# Main_Board.net
KiCad netlist of a schematic drawn in EAGLE
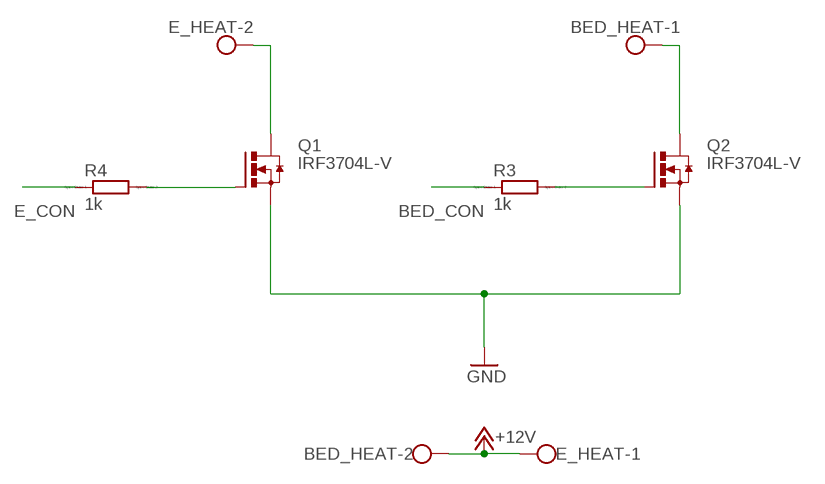
[diagram p0: schematic, sheet 1, part 1 of 2]
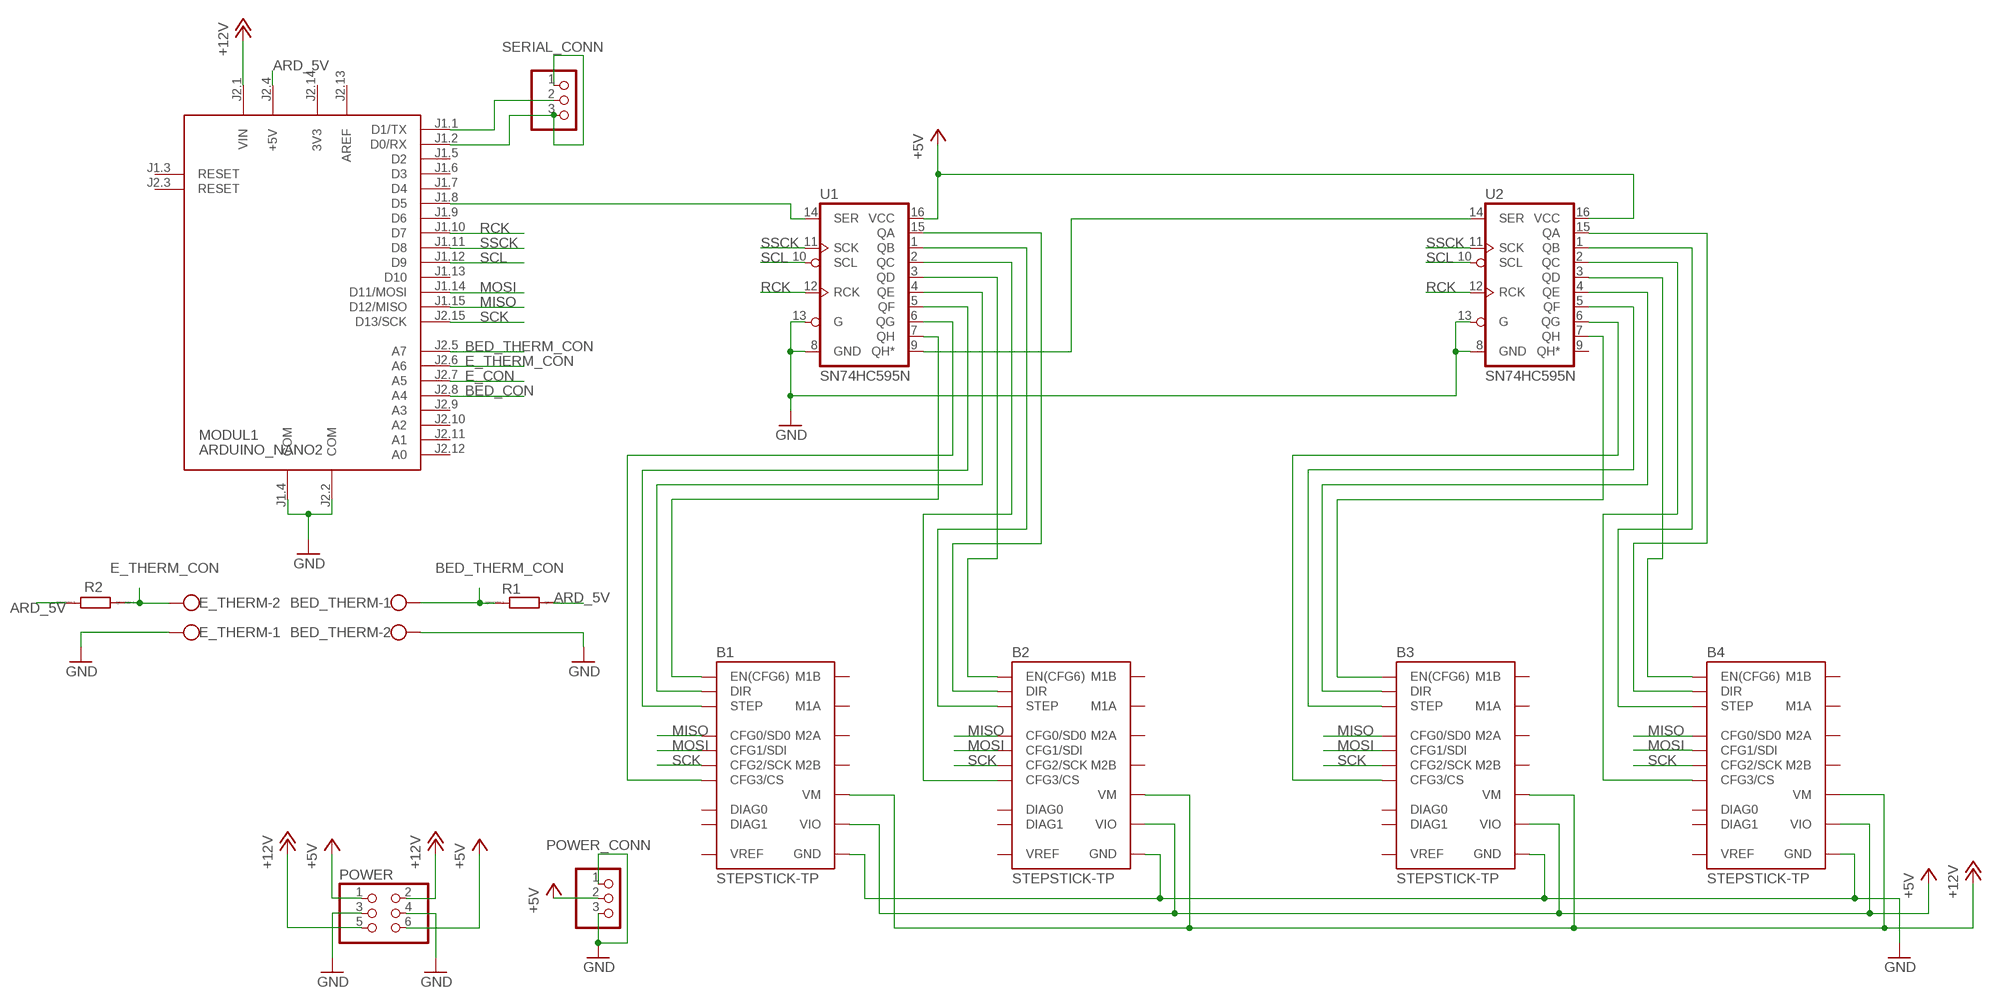
[diagram p1: schematic, sheet 1, part 2 of 2]

(export (version "E")
  (design (tool "Eeschema 10.0.6"))
  (components
    (comp (ref "B1")
      (value "STEPSTICK-TP")
      (footprint "eagle-import:STEPSTICK_TP")
      (libsource (lib "eagle-import") (part "STEPSTICK-TP"))
    )
    (comp (ref "B2")
      (value "STEPSTICK-TP")
      (footprint "eagle-import:STEPSTICK_TP")
      (libsource (lib "eagle-import") (part "STEPSTICK-TP"))
    )
    (comp (ref "B3")
      (value "STEPSTICK-TP")
      (footprint "eagle-import:STEPSTICK_TP")
      (libsource (lib "eagle-import") (part "STEPSTICK-TP"))
    )
    (comp (ref "B4")
      (value "STEPSTICK-TP")
      (footprint "eagle-import:STEPSTICK_TP")
      (libsource (lib "eagle-import") (part "STEPSTICK-TP"))
    )
    (comp (ref "BED_HEAT")
      (value "W237-102")
      (footprint "eagle-import:W237-102")
      (fields (field (name "MPN") "237-102"))
      (libsource (lib "eagle-import") (part "W237-102"))
    )
    (comp (ref "BED_THERM")
      (value "W237-102")
      (footprint "eagle-import:W237-102")
      (fields (field (name "MPN") "237-102"))
      (libsource (lib "eagle-import") (part "W237-102"))
    )
    (comp (ref "E_HEAT")
      (value "W237-102")
      (footprint "eagle-import:W237-102")
      (fields (field (name "MPN") "237-102"))
      (libsource (lib "eagle-import") (part "W237-102"))
    )
    (comp (ref "E_THERM")
      (value "W237-102")
      (footprint "eagle-import:W237-102")
      (fields (field (name "MPN") "237-102"))
      (libsource (lib "eagle-import") (part "W237-102"))
    )
    (comp (ref "MODUL1")
      (value "ARDUINO_NANO2")
      (footprint "eagle-import:ARDUINO_NANO2")
      (libsource (lib "eagle-import") (part "ARDUINO_NANO2"))
    )
    (comp (ref "POWER")
      (value "PINHD-2X3")
      (footprint "eagle-import:2X03")
      (libsource (lib "eagle-import") (part "PINHD-2X3"))
    )
    (comp (ref "POWER_CONN")
      (value "PINHD-1X3")
      (footprint "eagle-import:1X03")
      (libsource (lib "eagle-import") (part "PINHD-1X3"))
    )
    (comp (ref "Q1")
      (value "IRF3704L-V")
      (footprint "eagle-import:TO262-V")
      (libsource (lib "eagle-import") (part "IRF3704L-V"))
    )
    (comp (ref "Q2")
      (value "IRF3704L-V")
      (footprint "eagle-import:TO262-V")
      (libsource (lib "eagle-import") (part "IRF3704L-V"))
    )
    (comp (ref "R1")
      (value "R0204/7")
      (footprint "eagle-import:0204_7")
      (libsource (lib "eagle-import") (part "R0204/7"))
    )
    (comp (ref "R2")
      (value "R0204/7")
      (footprint "eagle-import:0204_7")
      (libsource (lib "eagle-import") (part "R0204/7"))
    )
    (comp (ref "R3")
      (value "1k")
      (footprint "eagle-import:0207_10")
      (libsource (lib "eagle-import") (part "R0207/10"))
    )
    (comp (ref "R4")
      (value "1k")
      (footprint "eagle-import:0207_10")
      (libsource (lib "eagle-import") (part "R0207/10"))
    )
    (comp (ref "SERIAL_CONN")
      (value "PINHD-1X3")
      (footprint "eagle-import:1X03")
      (libsource (lib "eagle-import") (part "PINHD-1X3"))
    )
    (comp (ref "U1")
      (value "SN74HC595N")
      (footprint "eagle-import:DIP16")
      (libsource (lib "eagle-import") (part "74595NHC"))
    )
    (comp (ref "U2")
      (value "SN74HC595N")
      (footprint "eagle-import:DIP16")
      (libsource (lib "eagle-import") (part "74595NHC"))
    )
  )
  (nets
    (net (code "1") (name "+5V") (class "Default")
      (node (ref "B1") (pin "VIO") (pinfunction "VIO_VIO") (pintype "power_in"))
      (node (ref "B2") (pin "VIO") (pinfunction "VIO_VIO") (pintype "power_in"))
      (node (ref "B3") (pin "VIO") (pinfunction "VIO_VIO") (pintype "power_in"))
      (node (ref "B4") (pin "VIO") (pinfunction "VIO_VIO") (pintype "power_in"))
      (node (ref "POWER") (pin "1") (pinfunction "1_1") (pintype "passive"))
      (node (ref "POWER") (pin "6") (pinfunction "6_6") (pintype "passive"))
      (node (ref "POWER_CONN") (pin "2") (pinfunction "2_2") (pintype "passive"))
      (node (ref "U1") (pin "16") (pinfunction "VCC_16") (pintype "power_in"))
      (node (ref "U2") (pin "16") (pinfunction "VCC_16") (pintype "power_in"))
    )
    (net (code "2") (name "+12V") (class "Default")
      (node (ref "B1") (pin "VM") (pinfunction "VM_VM") (pintype "power_in"))
      (node (ref "B2") (pin "VM") (pinfunction "VM_VM") (pintype "power_in"))
      (node (ref "B3") (pin "VM") (pinfunction "VM_VM") (pintype "power_in"))
      (node (ref "B4") (pin "VM") (pinfunction "VM_VM") (pintype "power_in"))
      (node (ref "BED_HEAT") (pin "2") (pinfunction "KL_2") (pintype "passive"))
      (node (ref "E_HEAT") (pin "1") (pinfunction "KL_1") (pintype "passive"))
      (node (ref "MODUL1") (pin "J2.1") (pinfunction "VIN_J2.1") (pintype "power_in"))
      (node (ref "POWER") (pin "2") (pinfunction "2_2") (pintype "passive"))
      (node (ref "POWER") (pin "5") (pinfunction "5_5") (pintype "passive"))
    )
    (net (code "3") (name "/3V3") (class "Default")
      (node (ref "MODUL1") (pin "J2.14") (pinfunction "3V3_J2.14") (pintype "power_in"))
    )
    (net (code "4") (name "/ARD_5V") (class "Default")
      (node (ref "MODUL1") (pin "J2.4") (pinfunction "+5V_J2.4") (pintype "power_in"))
      (node (ref "R1") (pin "2") (pinfunction "2_2") (pintype "passive"))
      (node (ref "R2") (pin "2") (pinfunction "2_2") (pintype "passive"))
    )
    (net (code "5") (name "/AREF") (class "Default")
      (node (ref "MODUL1") (pin "J2.13") (pinfunction "AREF_J2.13") (pintype "power_in"))
    )
    (net (code "6") (name "/BED_CON") (class "Default")
      (node (ref "MODUL1") (pin "J2.8") (pinfunction "A4_J2.8") (pintype "bidirectional"))
      (node (ref "R3") (pin "1") (pinfunction "1_1") (pintype "passive"))
    )
    (net (code "7") (name "/BED_THERM_CON") (class "Default")
      (node (ref "BED_THERM") (pin "1") (pinfunction "KL_1") (pintype "passive"))
      (node (ref "MODUL1") (pin "J2.5") (pinfunction "A7_J2.5") (pintype "bidirectional"))
      (node (ref "R1") (pin "1") (pinfunction "1_1") (pintype "passive"))
    )
    (net (code "8") (name "/E_CON") (class "Default")
      (node (ref "MODUL1") (pin "J2.7") (pinfunction "A5_J2.7") (pintype "bidirectional"))
      (node (ref "R4") (pin "1") (pinfunction "1_1") (pintype "passive"))
    )
    (net (code "9") (name "/E_THERM_CON") (class "Default")
      (node (ref "E_THERM") (pin "2") (pinfunction "KL_2") (pintype "passive"))
      (node (ref "MODUL1") (pin "J2.6") (pinfunction "A6_J2.6") (pintype "bidirectional"))
      (node (ref "R2") (pin "1") (pinfunction "1_1") (pintype "passive"))
    )
    (net (code "10") (name "/MISO") (class "Default")
      (node (ref "B1") (pin "NC/CFG0") (pinfunction "CFG0/SD0_NC/CFG0") (pintype "bidirectional"))
      (node (ref "B2") (pin "NC/CFG0") (pinfunction "CFG0/SD0_NC/CFG0") (pintype "bidirectional"))
      (node (ref "B3") (pin "NC/CFG0") (pinfunction "CFG0/SD0_NC/CFG0") (pintype "bidirectional"))
      (node (ref "B4") (pin "NC/CFG0") (pinfunction "CFG0/SD0_NC/CFG0") (pintype "bidirectional"))
      (node (ref "MODUL1") (pin "J1.15") (pinfunction "D12/MISO_J1.15") (pintype "bidirectional"))
    )
    (net (code "11") (name "/MOSI") (class "Default")
      (node (ref "B1") (pin "CFG1") (pinfunction "CFG1/SDI_CFG1") (pintype "bidirectional"))
      (node (ref "B2") (pin "CFG1") (pinfunction "CFG1/SDI_CFG1") (pintype "bidirectional"))
      (node (ref "B3") (pin "CFG1") (pinfunction "CFG1/SDI_CFG1") (pintype "bidirectional"))
      (node (ref "B4") (pin "CFG1") (pinfunction "CFG1/SDI_CFG1") (pintype "bidirectional"))
      (node (ref "MODUL1") (pin "J1.14") (pinfunction "D11/MOSI_J1.14") (pintype "bidirectional"))
    )
    (net (code "12") (name "/RCK") (class "Default")
      (node (ref "MODUL1") (pin "J1.10") (pinfunction "D7_J1.10") (pintype "bidirectional"))
      (node (ref "U1") (pin "12") (pinfunction "RCK_12") (pintype "input"))
      (node (ref "U2") (pin "12") (pinfunction "RCK_12") (pintype "input"))
    )
    (net (code "13") (name "/SCK") (class "Default")
      (node (ref "B1") (pin "CFG2") (pinfunction "CFG2/SCK_CFG2") (pintype "bidirectional"))
      (node (ref "B2") (pin "CFG2") (pinfunction "CFG2/SCK_CFG2") (pintype "bidirectional"))
      (node (ref "B3") (pin "CFG2") (pinfunction "CFG2/SCK_CFG2") (pintype "bidirectional"))
      (node (ref "B4") (pin "CFG2") (pinfunction "CFG2/SCK_CFG2") (pintype "bidirectional"))
      (node (ref "MODUL1") (pin "J2.15") (pinfunction "D13/SCK_J2.15") (pintype "bidirectional"))
    )
    (net (code "14") (name "/SCL") (class "Default")
      (node (ref "MODUL1") (pin "J1.12") (pinfunction "D9_J1.12") (pintype "bidirectional"))
      (node (ref "U1") (pin "10") (pinfunction "SCL_10") (pintype "input"))
      (node (ref "U2") (pin "10") (pinfunction "SCL_10") (pintype "input"))
    )
    (net (code "15") (name "/SSCK") (class "Default")
      (node (ref "MODUL1") (pin "J1.11") (pinfunction "D8_J1.11") (pintype "bidirectional"))
      (node (ref "U1") (pin "11") (pinfunction "SCK_11") (pintype "input"))
      (node (ref "U2") (pin "11") (pinfunction "SCK_11") (pintype "input"))
    )
    (net (code "16") (name "GND") (class "Default")
      (node (ref "B1") (pin "GND@1") (pinfunction "GND_GND@1") (pintype "power_in"))
      (node (ref "B1") (pin "GND@2") (pinfunction "GND_GND@2") (pintype "power_in"))
      (node (ref "B2") (pin "GND@1") (pinfunction "GND_GND@1") (pintype "power_in"))
      (node (ref "B2") (pin "GND@2") (pinfunction "GND_GND@2") (pintype "power_in"))
      (node (ref "B3") (pin "GND@1") (pinfunction "GND_GND@1") (pintype "power_in"))
      (node (ref "B3") (pin "GND@2") (pinfunction "GND_GND@2") (pintype "power_in"))
      (node (ref "B4") (pin "GND@1") (pinfunction "GND_GND@1") (pintype "power_in"))
      (node (ref "B4") (pin "GND@2") (pinfunction "GND_GND@2") (pintype "power_in"))
      (node (ref "BED_THERM") (pin "2") (pinfunction "KL_2") (pintype "passive"))
      (node (ref "E_THERM") (pin "1") (pinfunction "KL_1") (pintype "passive"))
      (node (ref "MODUL1") (pin "J1.4") (pinfunction "COM_J1.4") (pintype "power_in"))
      (node (ref "MODUL1") (pin "J2.2") (pinfunction "COM_J2.2") (pintype "power_in"))
      (node (ref "POWER") (pin "3") (pinfunction "3_3") (pintype "passive"))
      (node (ref "POWER") (pin "4") (pinfunction "4_4") (pintype "passive"))
      (node (ref "POWER_CONN") (pin "1") (pinfunction "1_1") (pintype "passive"))
      (node (ref "POWER_CONN") (pin "3") (pinfunction "3_3") (pintype "passive"))
      (node (ref "Q1") (pin "3") (pinfunction "S_3") (pintype "passive"))
      (node (ref "Q2") (pin "3") (pinfunction "S_3") (pintype "passive"))
      (node (ref "U1") (pin "13") (pinfunction "G_13") (pintype "input"))
      (node (ref "U1") (pin "8") (pinfunction "GND_8") (pintype "power_in"))
      (node (ref "U2") (pin "13") (pinfunction "G_13") (pintype "input"))
      (node (ref "U2") (pin "8") (pinfunction "GND_8") (pintype "power_in"))
    )
    (net (code "17") (name "Net-(B1-CFG3{slash}CS)") (class "Default")
      (node (ref "B1") (pin "CFG3") (pinfunction "CFG3/CS_CFG3") (pintype "bidirectional"))
      (node (ref "U1") (pin "6") (pinfunction "QG_6") (pintype "tri_state"))
    )
    (net (code "18") (name "Net-(B1-EN(CFG6))") (class "Default")
      (node (ref "B1") (pin "EN") (pinfunction "EN(CFG6)_EN") (pintype "bidirectional"))
      (node (ref "U1") (pin "7") (pinfunction "QH_7") (pintype "tri_state"))
    )
    (net (code "19") (name "Net-(B2-CFG3{slash}CS)") (class "Default")
      (node (ref "B2") (pin "CFG3") (pinfunction "CFG3/CS_CFG3") (pintype "bidirectional"))
      (node (ref "U1") (pin "2") (pinfunction "QC_2") (pintype "tri_state"))
    )
    (net (code "20") (name "Net-(B2-EN(CFG6))") (class "Default")
      (node (ref "B2") (pin "EN") (pinfunction "EN(CFG6)_EN") (pintype "bidirectional"))
      (node (ref "U1") (pin "3") (pinfunction "QD_3") (pintype "tri_state"))
    )
    (net (code "21") (name "Net-(B3-CFG3{slash}CS)") (class "Default")
      (node (ref "B3") (pin "CFG3") (pinfunction "CFG3/CS_CFG3") (pintype "bidirectional"))
      (node (ref "U2") (pin "6") (pinfunction "QG_6") (pintype "tri_state"))
    )
    (net (code "22") (name "Net-(B3-EN(CFG6))") (class "Default")
      (node (ref "B3") (pin "EN") (pinfunction "EN(CFG6)_EN") (pintype "bidirectional"))
      (node (ref "U2") (pin "7") (pinfunction "QH_7") (pintype "tri_state"))
    )
    (net (code "23") (name "Net-(B4-CFG3{slash}CS)") (class "Default")
      (node (ref "B4") (pin "CFG3") (pinfunction "CFG3/CS_CFG3") (pintype "bidirectional"))
      (node (ref "U2") (pin "2") (pinfunction "QC_2") (pintype "tri_state"))
    )
    (net (code "24") (name "Net-(B4-EN(CFG6))") (class "Default")
      (node (ref "B4") (pin "EN") (pinfunction "EN(CFG6)_EN") (pintype "bidirectional"))
      (node (ref "U2") (pin "3") (pinfunction "QD_3") (pintype "tri_state"))
    )
    (net (code "25") (name "Net-(BED_HEATA-KL)") (class "Default")
      (node (ref "BED_HEAT") (pin "1") (pinfunction "KL_1") (pintype "passive"))
      (node (ref "Q2") (pin "2") (pinfunction "D_2") (pintype "passive"))
    )
    (net (code "26") (name "Net-(E_HEATB-KL)") (class "Default")
      (node (ref "E_HEAT") (pin "2") (pinfunction "KL_2") (pintype "passive"))
      (node (ref "Q1") (pin "2") (pinfunction "D_2") (pintype "passive"))
    )
    (net (code "27") (name "Net-(MODUL1-D0{slash}RX)") (class "Default")
      (node (ref "MODUL1") (pin "J1.2") (pinfunction "D0/RX_J1.2") (pintype "bidirectional"))
      (node (ref "SERIAL_CONN") (pin "1") (pinfunction "1_1") (pintype "passive"))
      (node (ref "SERIAL_CONN") (pin "3") (pinfunction "3_3") (pintype "passive"))
    )
    (net (code "28") (name "Net-(MODUL1-D1{slash}TX)") (class "Default")
      (node (ref "MODUL1") (pin "J1.1") (pinfunction "D1/TX_J1.1") (pintype "bidirectional"))
      (node (ref "SERIAL_CONN") (pin "2") (pinfunction "2_2") (pintype "passive"))
    )
    (net (code "29") (name "Net-(MODUL1-D5)") (class "Default")
      (node (ref "MODUL1") (pin "J1.8") (pinfunction "D5_J1.8") (pintype "bidirectional"))
      (node (ref "U1") (pin "14") (pinfunction "SER_14") (pintype "input"))
    )
    (net (code "30") (name "Net-(Q1-G)") (class "Default")
      (node (ref "Q1") (pin "1") (pinfunction "G_1") (pintype "passive"))
      (node (ref "R4") (pin "2") (pinfunction "2_2") (pintype "passive"))
    )
    (net (code "31") (name "Net-(Q2-G)") (class "Default")
      (node (ref "Q2") (pin "1") (pinfunction "G_1") (pintype "passive"))
      (node (ref "R3") (pin "2") (pinfunction "2_2") (pintype "passive"))
    )
    (net (code "32") (name "Net-(U1-QA)") (class "Default")
      (node (ref "B2") (pin "DIR") (pinfunction "DIR_DIR") (pintype "bidirectional"))
      (node (ref "U1") (pin "15") (pinfunction "QA_15") (pintype "tri_state"))
    )
    (net (code "33") (name "Net-(U1-QB)") (class "Default")
      (node (ref "B2") (pin "STEP") (pinfunction "STEP_STEP") (pintype "bidirectional"))
      (node (ref "U1") (pin "1") (pinfunction "QB_1") (pintype "tri_state"))
    )
    (net (code "34") (name "Net-(U1-QE)") (class "Default")
      (node (ref "B1") (pin "DIR") (pinfunction "DIR_DIR") (pintype "bidirectional"))
      (node (ref "U1") (pin "4") (pinfunction "QE_4") (pintype "tri_state"))
    )
    (net (code "35") (name "Net-(U1-QF)") (class "Default")
      (node (ref "B1") (pin "STEP") (pinfunction "STEP_STEP") (pintype "bidirectional"))
      (node (ref "U1") (pin "5") (pinfunction "QF_5") (pintype "tri_state"))
    )
    (net (code "36") (name "Net-(U1-QH*)") (class "Default")
      (node (ref "U1") (pin "9") (pinfunction "QH*_9") (pintype "tri_state"))
      (node (ref "U2") (pin "14") (pinfunction "SER_14") (pintype "input"))
    )
    (net (code "37") (name "Net-(U2-QA)") (class "Default")
      (node (ref "B4") (pin "DIR") (pinfunction "DIR_DIR") (pintype "bidirectional"))
      (node (ref "U2") (pin "15") (pinfunction "QA_15") (pintype "tri_state"))
    )
    (net (code "38") (name "Net-(U2-QB)") (class "Default")
      (node (ref "B4") (pin "STEP") (pinfunction "STEP_STEP") (pintype "bidirectional"))
      (node (ref "U2") (pin "1") (pinfunction "QB_1") (pintype "tri_state"))
    )
    (net (code "39") (name "Net-(U2-QE)") (class "Default")
      (node (ref "B3") (pin "DIR") (pinfunction "DIR_DIR") (pintype "bidirectional"))
      (node (ref "U2") (pin "4") (pinfunction "QE_4") (pintype "tri_state"))
    )
    (net (code "40") (name "Net-(U2-QF)") (class "Default")
      (node (ref "B3") (pin "STEP") (pinfunction "STEP_STEP") (pintype "bidirectional"))
      (node (ref "U2") (pin "5") (pinfunction "QF_5") (pintype "tri_state"))
    )
    (net (code "41") (name "unconnected-(B1-PadDIAG0)") (class "Default")
      (node (ref "B1") (pin "DIAG0") (pinfunction "DIAG0_DIAG0") (pintype "bidirectional"))
    )
    (net (code "42") (name "unconnected-(B1-PadDIAG1)") (class "Default")
      (node (ref "B1") (pin "DIAG1") (pinfunction "DIAG1_DIAG1") (pintype "bidirectional"))
    )
    (net (code "43") (name "unconnected-(B1-PadM1A)") (class "Default")
      (node (ref "B1") (pin "M1A") (pinfunction "M1A_M1A") (pintype "output"))
    )
    (net (code "44") (name "unconnected-(B1-PadM1B)") (class "Default")
      (node (ref "B1") (pin "M1B") (pinfunction "M1B_M1B") (pintype "output"))
    )
    (net (code "45") (name "unconnected-(B1-PadM2A)") (class "Default")
      (node (ref "B1") (pin "M2A") (pinfunction "M2A_M2A") (pintype "output"))
    )
    (net (code "46") (name "unconnected-(B1-PadM2B)") (class "Default")
      (node (ref "B1") (pin "M2B") (pinfunction "M2B_M2B") (pintype "output"))
    )
    (net (code "47") (name "unconnected-(B1-PadVREF)") (class "Default")
      (node (ref "B1") (pin "VREF") (pinfunction "VREF_VREF") (pintype "passive"))
    )
    (net (code "48") (name "unconnected-(B2-PadDIAG0)") (class "Default")
      (node (ref "B2") (pin "DIAG0") (pinfunction "DIAG0_DIAG0") (pintype "bidirectional"))
    )
    (net (code "49") (name "unconnected-(B2-PadDIAG1)") (class "Default")
      (node (ref "B2") (pin "DIAG1") (pinfunction "DIAG1_DIAG1") (pintype "bidirectional"))
    )
    (net (code "50") (name "unconnected-(B2-PadM1A)") (class "Default")
      (node (ref "B2") (pin "M1A") (pinfunction "M1A_M1A") (pintype "output"))
    )
    (net (code "51") (name "unconnected-(B2-PadM1B)") (class "Default")
      (node (ref "B2") (pin "M1B") (pinfunction "M1B_M1B") (pintype "output"))
    )
    (net (code "52") (name "unconnected-(B2-PadM2A)") (class "Default")
      (node (ref "B2") (pin "M2A") (pinfunction "M2A_M2A") (pintype "output"))
    )
    (net (code "53") (name "unconnected-(B2-PadM2B)") (class "Default")
      (node (ref "B2") (pin "M2B") (pinfunction "M2B_M2B") (pintype "output"))
    )
    (net (code "54") (name "unconnected-(B2-PadVREF)") (class "Default")
      (node (ref "B2") (pin "VREF") (pinfunction "VREF_VREF") (pintype "passive"))
    )
    (net (code "55") (name "unconnected-(B3-PadDIAG0)") (class "Default")
      (node (ref "B3") (pin "DIAG0") (pinfunction "DIAG0_DIAG0") (pintype "bidirectional"))
    )
    (net (code "56") (name "unconnected-(B3-PadDIAG1)") (class "Default")
      (node (ref "B3") (pin "DIAG1") (pinfunction "DIAG1_DIAG1") (pintype "bidirectional"))
    )
    (net (code "57") (name "unconnected-(B3-PadM1A)") (class "Default")
      (node (ref "B3") (pin "M1A") (pinfunction "M1A_M1A") (pintype "output"))
    )
    (net (code "58") (name "unconnected-(B3-PadM1B)") (class "Default")
      (node (ref "B3") (pin "M1B") (pinfunction "M1B_M1B") (pintype "output"))
    )
    (net (code "59") (name "unconnected-(B3-PadM2A)") (class "Default")
      (node (ref "B3") (pin "M2A") (pinfunction "M2A_M2A") (pintype "output"))
    )
    (net (code "60") (name "unconnected-(B3-PadM2B)") (class "Default")
      (node (ref "B3") (pin "M2B") (pinfunction "M2B_M2B") (pintype "output"))
    )
    (net (code "61") (name "unconnected-(B3-PadVREF)") (class "Default")
      (node (ref "B3") (pin "VREF") (pinfunction "VREF_VREF") (pintype "passive"))
    )
    (net (code "62") (name "unconnected-(B4-PadDIAG0)") (class "Default")
      (node (ref "B4") (pin "DIAG0") (pinfunction "DIAG0_DIAG0") (pintype "bidirectional"))
    )
    (net (code "63") (name "unconnected-(B4-PadDIAG1)") (class "Default")
      (node (ref "B4") (pin "DIAG1") (pinfunction "DIAG1_DIAG1") (pintype "bidirectional"))
    )
    (net (code "64") (name "unconnected-(B4-PadM1A)") (class "Default")
      (node (ref "B4") (pin "M1A") (pinfunction "M1A_M1A") (pintype "output"))
    )
    (net (code "65") (name "unconnected-(B4-PadM1B)") (class "Default")
      (node (ref "B4") (pin "M1B") (pinfunction "M1B_M1B") (pintype "output"))
    )
    (net (code "66") (name "unconnected-(B4-PadM2A)") (class "Default")
      (node (ref "B4") (pin "M2A") (pinfunction "M2A_M2A") (pintype "output"))
    )
    (net (code "67") (name "unconnected-(B4-PadM2B)") (class "Default")
      (node (ref "B4") (pin "M2B") (pinfunction "M2B_M2B") (pintype "output"))
    )
    (net (code "68") (name "unconnected-(B4-PadVREF)") (class "Default")
      (node (ref "B4") (pin "VREF") (pinfunction "VREF_VREF") (pintype "passive"))
    )
    (net (code "69") (name "unconnected-(MODUL1-A0-PadJ2.12)") (class "Default")
      (node (ref "MODUL1") (pin "J2.12") (pinfunction "A0_J2.12") (pintype "bidirectional"))
    )
    (net (code "70") (name "unconnected-(MODUL1-A1-PadJ2.11)") (class "Default")
      (node (ref "MODUL1") (pin "J2.11") (pinfunction "A1_J2.11") (pintype "bidirectional"))
    )
    (net (code "71") (name "unconnected-(MODUL1-A2-PadJ2.10)") (class "Default")
      (node (ref "MODUL1") (pin "J2.10") (pinfunction "A2_J2.10") (pintype "bidirectional"))
    )
    (net (code "72") (name "unconnected-(MODUL1-A3-PadJ2.9)") (class "Default")
      (node (ref "MODUL1") (pin "J2.9") (pinfunction "A3_J2.9") (pintype "bidirectional"))
    )
    (net (code "73") (name "unconnected-(MODUL1-D2-PadJ1.5)") (class "Default")
      (node (ref "MODUL1") (pin "J1.5") (pinfunction "D2_J1.5") (pintype "bidirectional"))
    )
    (net (code "74") (name "unconnected-(MODUL1-D3-PadJ1.6)") (class "Default")
      (node (ref "MODUL1") (pin "J1.6") (pinfunction "D3_J1.6") (pintype "bidirectional"))
    )
    (net (code "75") (name "unconnected-(MODUL1-D4-PadJ1.7)") (class "Default")
      (node (ref "MODUL1") (pin "J1.7") (pinfunction "D4_J1.7") (pintype "bidirectional"))
    )
    (net (code "76") (name "unconnected-(MODUL1-D6-PadJ1.9)") (class "Default")
      (node (ref "MODUL1") (pin "J1.9") (pinfunction "D6_J1.9") (pintype "bidirectional"))
    )
    (net (code "77") (name "unconnected-(MODUL1-D10-PadJ1.13)") (class "Default")
      (node (ref "MODUL1") (pin "J1.13") (pinfunction "D10_J1.13") (pintype "bidirectional"))
    )
    (net (code "78") (name "unconnected-(MODUL1-RESET-PadJ1.3)") (class "Default")
      (node (ref "MODUL1") (pin "J1.3") (pinfunction "RESET_J1.3") (pintype "bidirectional"))
    )
    (net (code "79") (name "unconnected-(MODUL1-RESET-PadJ2.3)") (class "Default")
      (node (ref "MODUL1") (pin "J2.3") (pinfunction "RESET_J2.3") (pintype "bidirectional"))
    )
    (net (code "80") (name "unconnected-(U2-QH*-Pad9)") (class "Default")
      (node (ref "U2") (pin "9") (pinfunction "QH*_9") (pintype "tri_state"))
    )
  )
)
